# STM_TEST.net
KiCad netlist of a schematic drawn in EAGLE
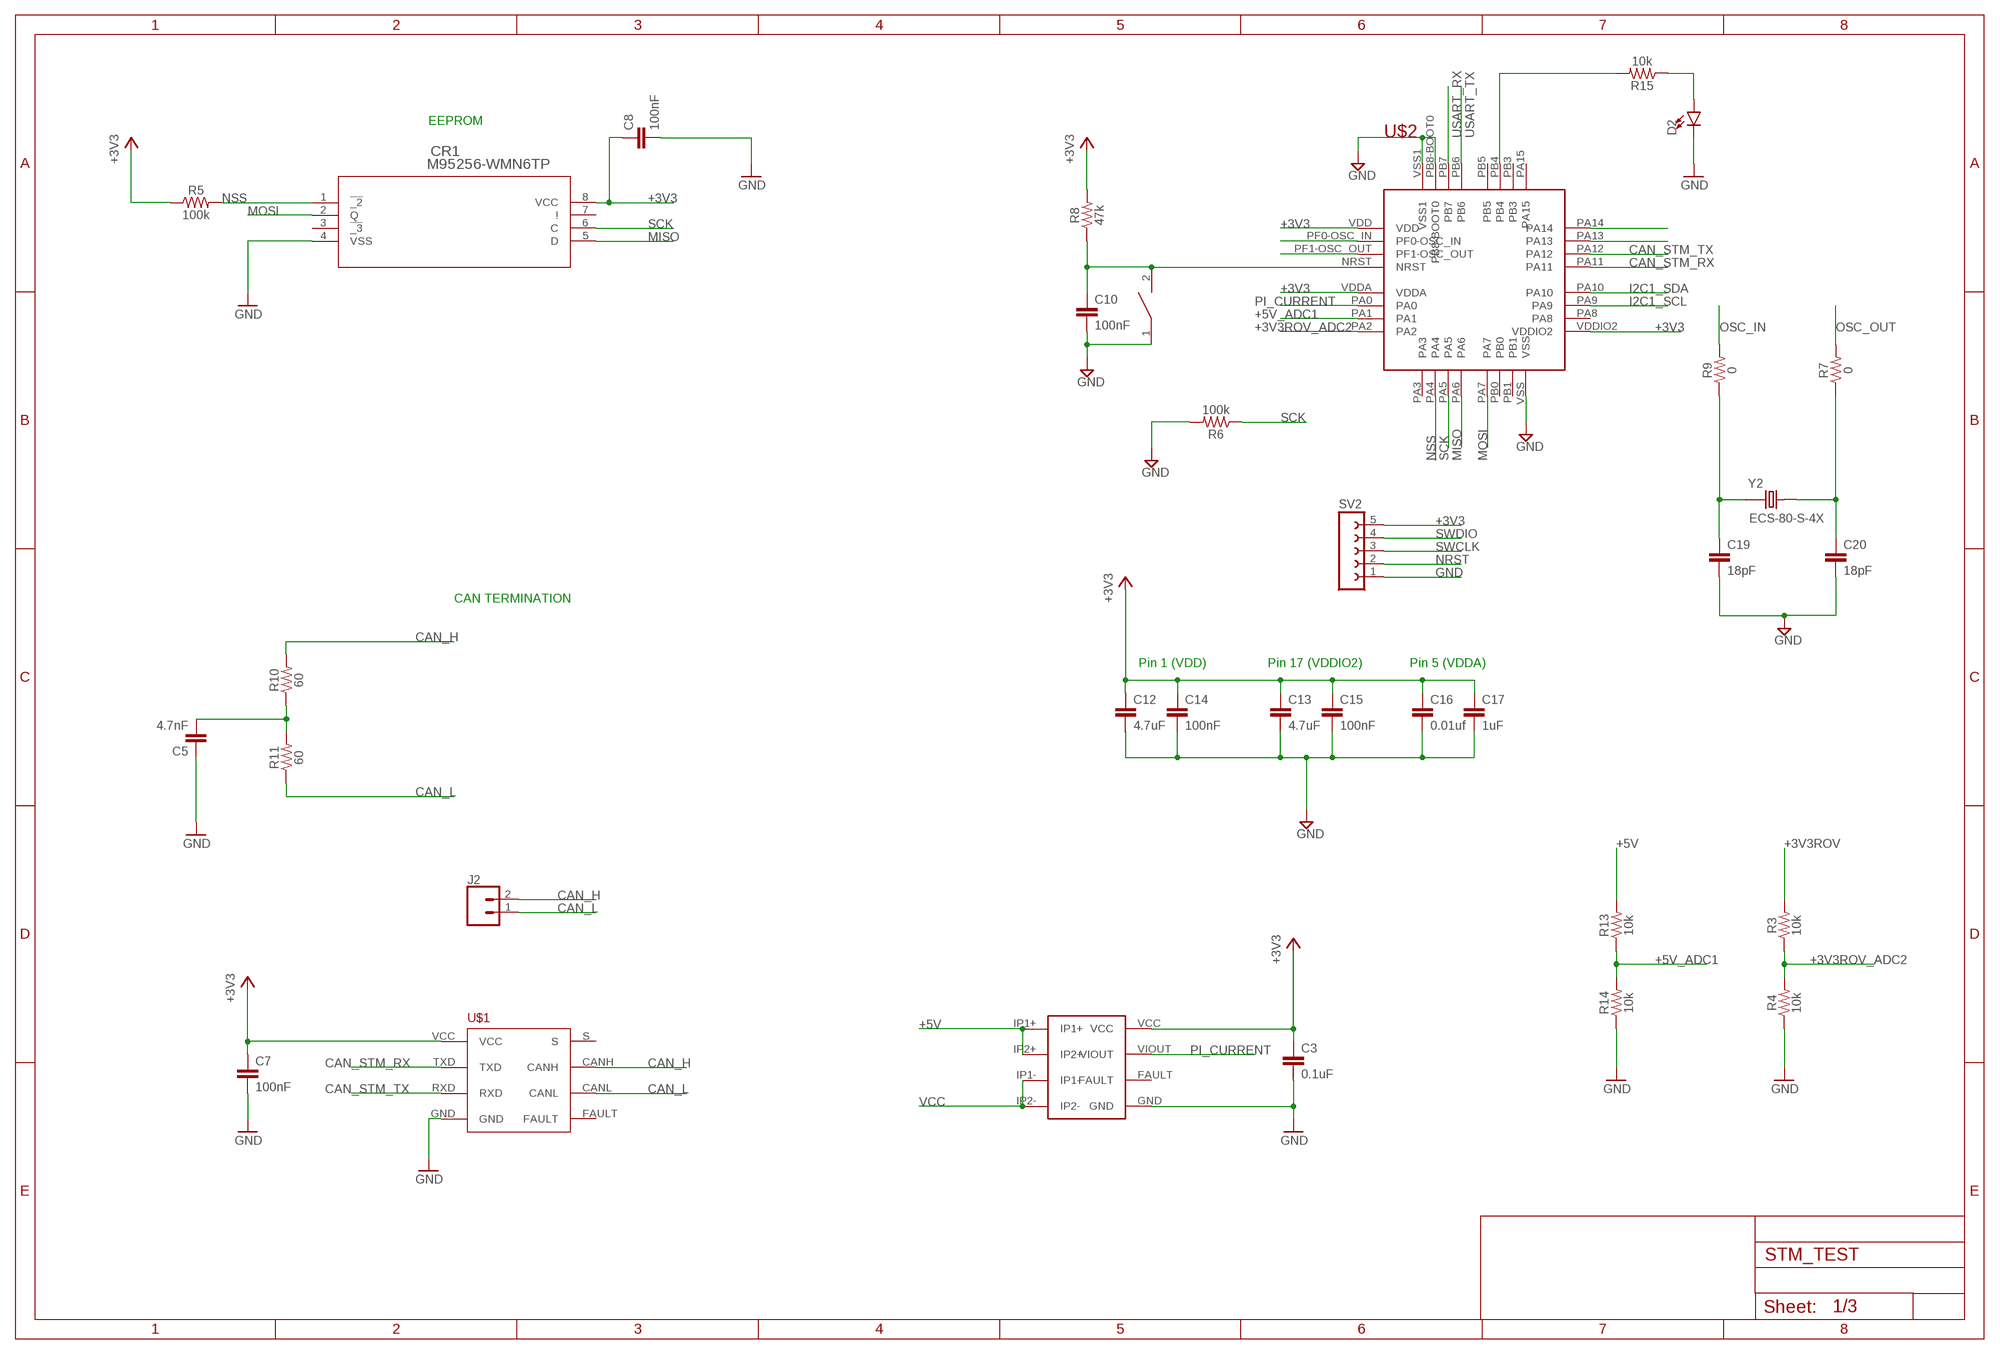
[diagram p0: schematic, sheet 1]
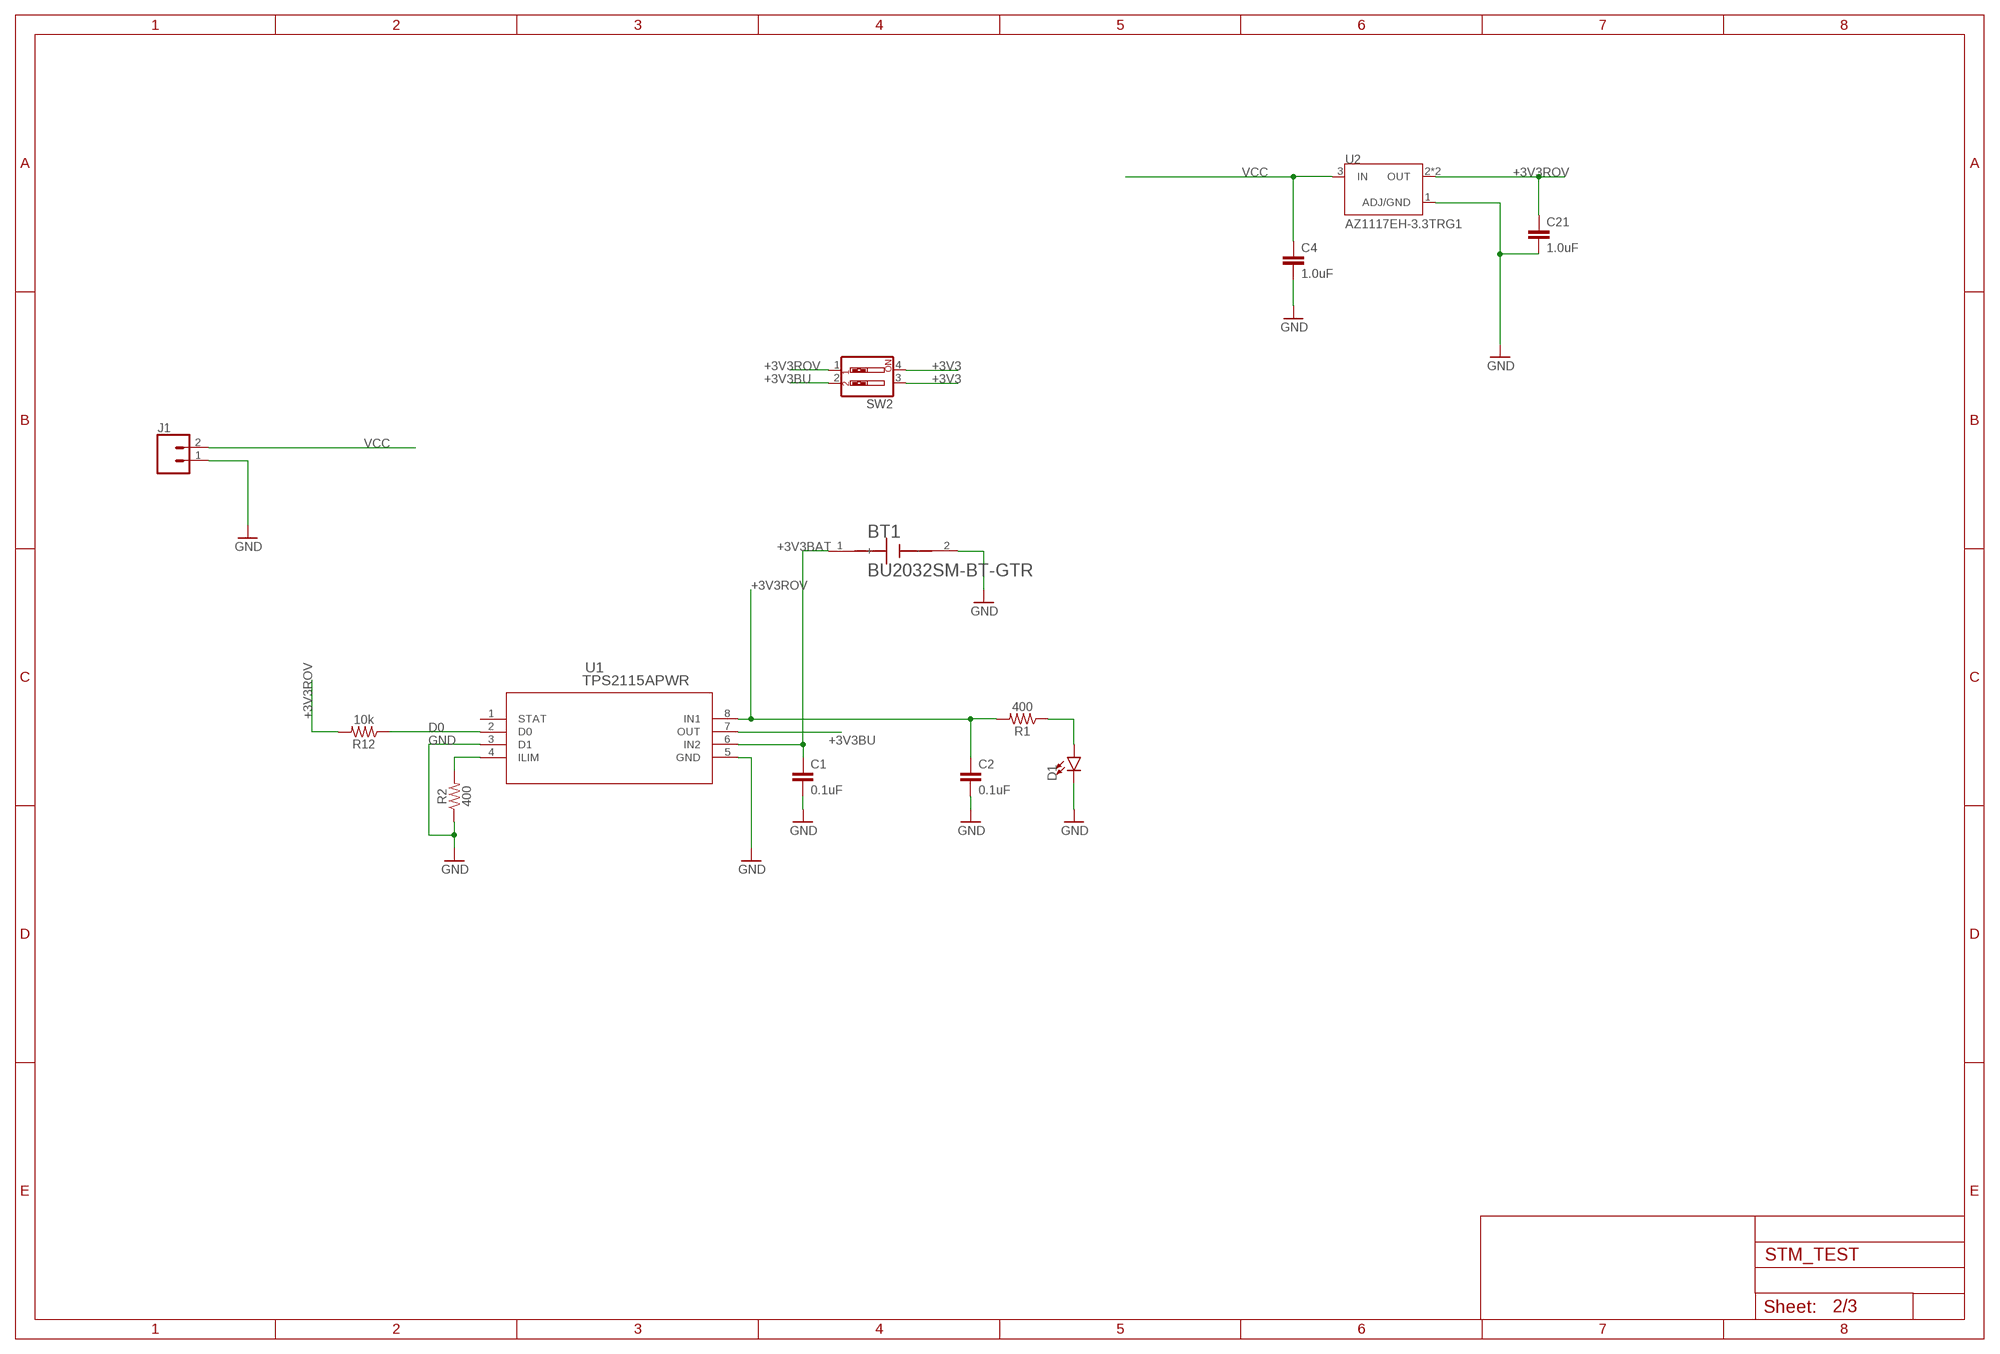
[diagram p1: schematic, sheet 2]
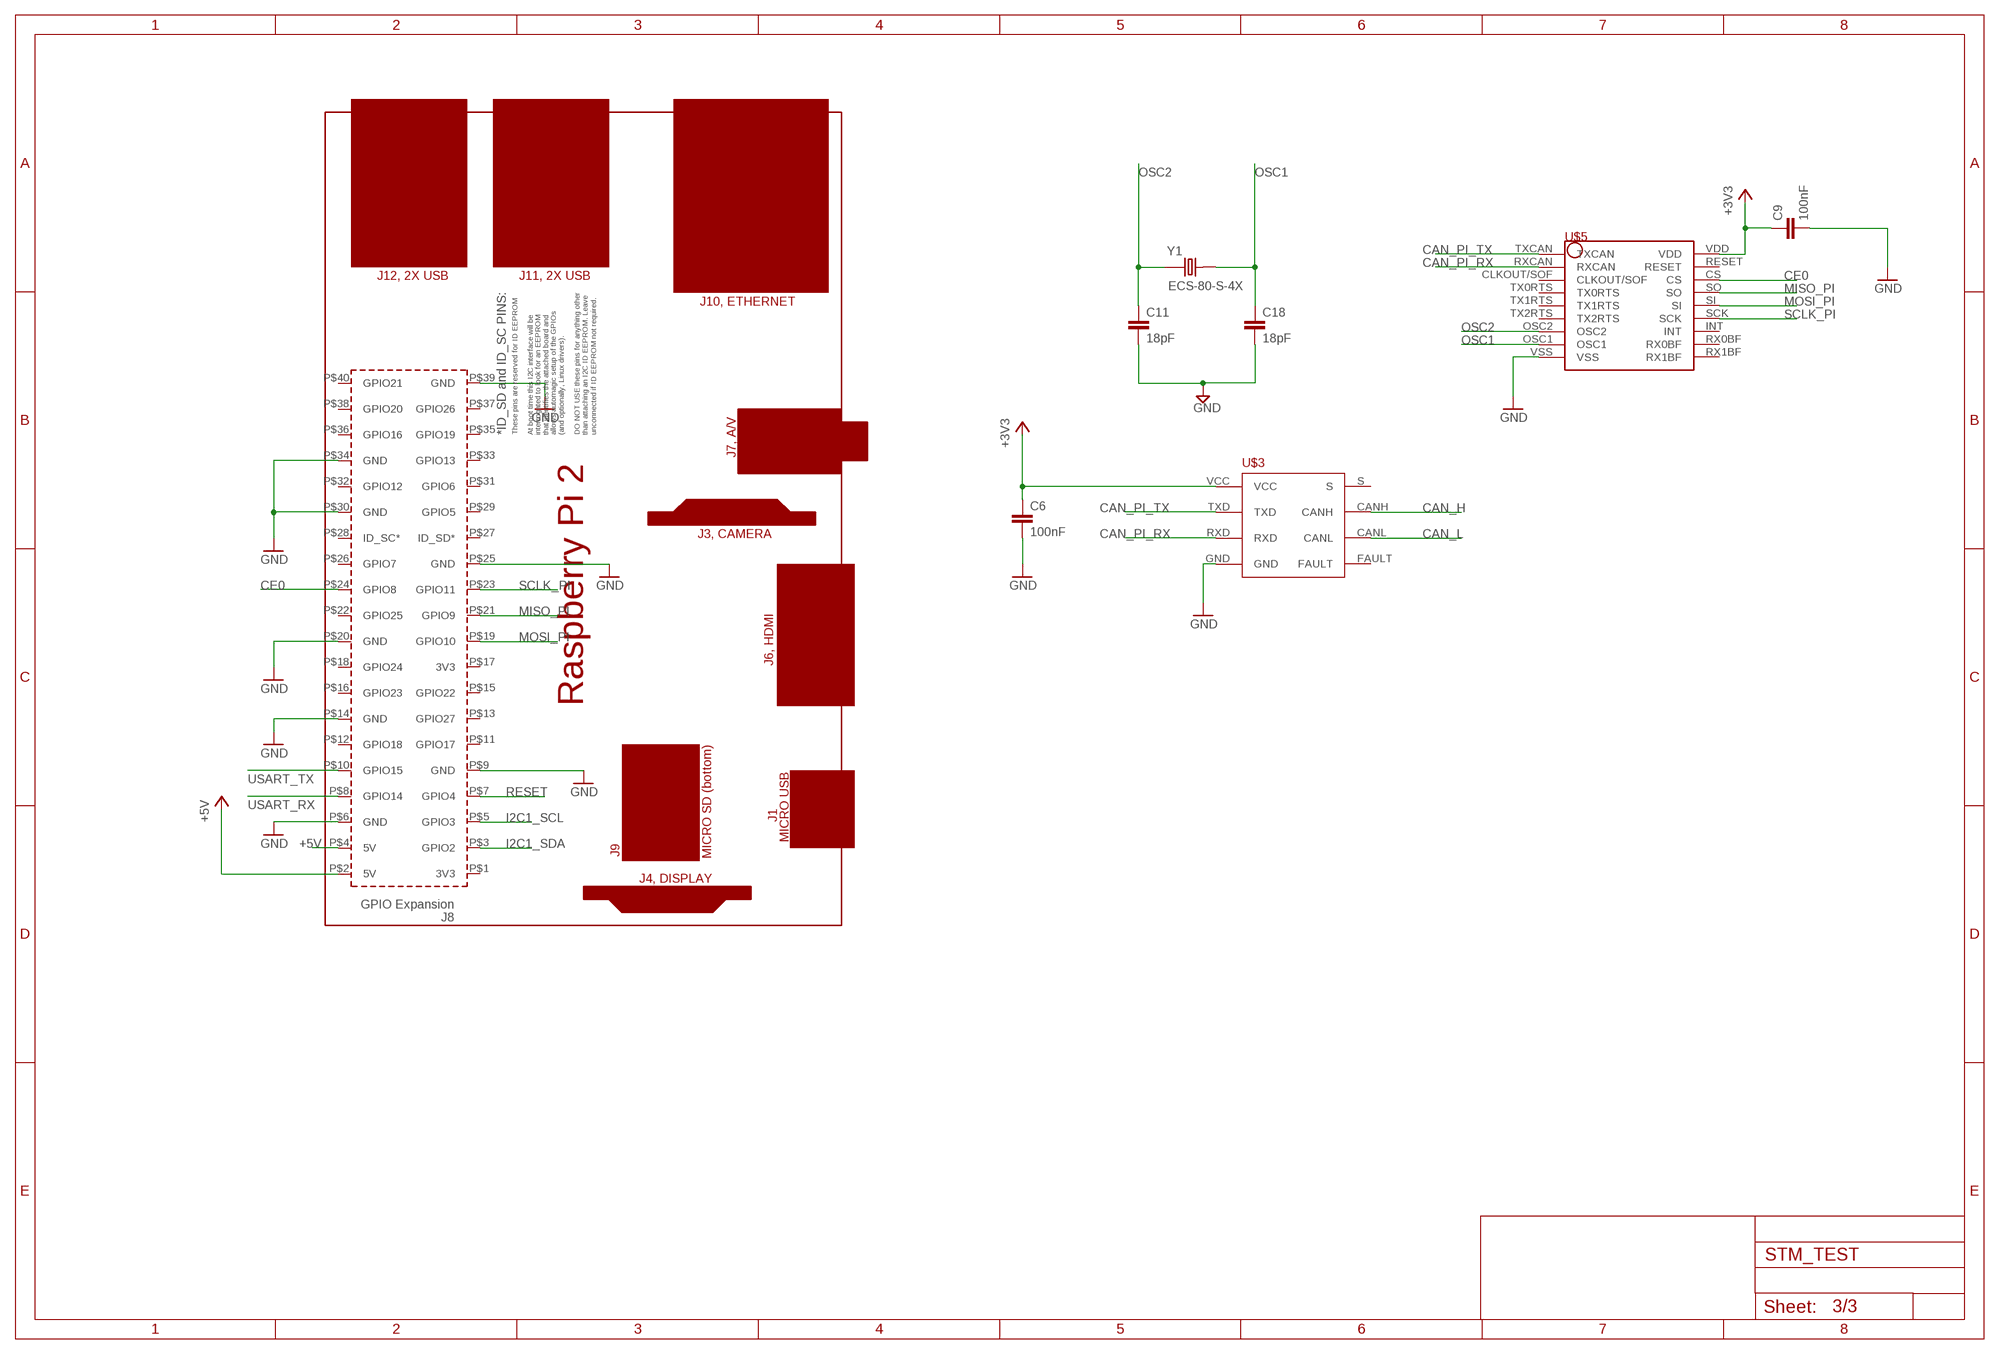
[diagram p2: schematic, sheet 3]

(export (version "E")
  (design (tool "Eeschema 10.0.6"))
  (components
    (comp (ref "C6")
      (value "100nF")
      (footprint "eagle-import:0603")
      (libsource (lib "eagle-import") (part "4.7UF0603"))
    )
    (comp (ref "C9")
      (value "100nF")
      (footprint "eagle-import:0603")
      (libsource (lib "eagle-import") (part "4.7UF0603"))
    )
    (comp (ref "C11")
      (value "18pF")
      (footprint "eagle-import:0603")
      (libsource (lib "eagle-import") (part "4.7UF0603"))
    )
    (comp (ref "C18")
      (value "18pF")
      (footprint "eagle-import:0603")
      (libsource (lib "eagle-import") (part "4.7UF0603"))
    )
    (comp (ref "PCB1")
      (value "RPI2")
      (footprint "eagle-import:RPI2")
      (libsource (lib "eagle-import") (part "RPI2"))
    )
    (comp (ref "U$3")
      (value "TCAN337D")
      (footprint "eagle-import:TCAN337D")
      (libsource (lib "eagle-import") (part "TCAN337D"))
    )
    (comp (ref "U$5")
      (value "MCP2515")
      (footprint "eagle-import:MCP2515")
      (libsource (lib "eagle-import") (part "MCP2515"))
    )
    (comp (ref "Y1")
      (value "ECS-80-S-4X")
      (footprint "eagle-import:XTAL_ECS-80-S-4X")
      (fields (field (name "DIGI-KEY_PART_NUMBER") "X1057-ND") (field (name "MF") "ECS International"))
      (libsource (lib "eagle-import") (part "ECS-80-S-4X"))
    )
    (comp (ref "C3")
      (value "0.1uF")
      (footprint "eagle-import:0603")
      (libsource (lib "eagle-import") (part "4.7UF0603"))
    )
    (comp (ref "C5")
      (value "4.7nF")
      (footprint "eagle-import:0603")
      (libsource (lib "eagle-import") (part "0.1UF-0603-25V-(+80/-20%)"))
    )
    (comp (ref "C7")
      (value "100nF")
      (footprint "eagle-import:0603")
      (libsource (lib "eagle-import") (part "4.7UF0603"))
    )
    (comp (ref "C8")
      (value "100nF")
      (footprint "eagle-import:0603")
      (libsource (lib "eagle-import") (part "4.7UF0603"))
    )
    (comp (ref "C10")
      (value "100nF")
      (footprint "eagle-import:0603")
      (libsource (lib "eagle-import") (part "4.7UF0603"))
    )
    (comp (ref "C12")
      (value "4.7uF")
      (footprint "eagle-import:0603")
      (libsource (lib "eagle-import") (part "4.7UF0603"))
    )
    (comp (ref "C13")
      (value "4.7uF")
      (footprint "eagle-import:0603")
      (libsource (lib "eagle-import") (part "4.7UF0603"))
    )
    (comp (ref "C14")
      (value "100nF")
      (footprint "eagle-import:0603")
      (libsource (lib "eagle-import") (part "4.7UF0603"))
    )
    (comp (ref "C15")
      (value "100nF")
      (footprint "eagle-import:0603")
      (libsource (lib "eagle-import") (part "4.7UF0603"))
    )
    (comp (ref "C16")
      (value "0.01uf")
      (footprint "eagle-import:0603")
      (libsource (lib "eagle-import") (part "4.7UF0603"))
    )
    (comp (ref "C17")
      (value "1uF")
      (footprint "eagle-import:0603")
      (libsource (lib "eagle-import") (part "4.7UF0603"))
    )
    (comp (ref "C19")
      (value "18pF")
      (footprint "eagle-import:0603")
      (libsource (lib "eagle-import") (part "4.7UF0603"))
    )
    (comp (ref "C20")
      (value "18pF")
      (footprint "eagle-import:0603")
      (libsource (lib "eagle-import") (part "4.7UF0603"))
    )
    (comp (ref "CR1")
      (value "M95256-WMN6TP")
      (footprint "eagle-import:SO-8")
      (fields (field (name "MANUFACTURER_PART_NUMBER") "M95256WMN6TP"))
      (libsource (lib "eagle-import") (part "M95256-WMN6TP"))
    )
    (comp (ref "D2")
      (value "LED0603")
      (footprint "eagle-import:LED-0603")
      (libsource (lib "eagle-import") (part "LED0603"))
    )
    (comp (ref "J2")
      (value "CONN_02")
      (footprint "eagle-import:1X02")
      (libsource (lib "eagle-import") (part "CONN_02"))
    )
    (comp (ref "R3")
      (value "10k")
      (footprint "eagle-import:0603")
      (libsource (lib "eagle-import") (part "1KOHM-0603-1/10W-1%"))
    )
    (comp (ref "R4")
      (value "10k")
      (footprint "eagle-import:0603")
      (libsource (lib "eagle-import") (part "1KOHM-0603-1/10W-1%"))
    )
    (comp (ref "R5")
      (value "100k")
      (footprint "eagle-import:0603")
      (libsource (lib "eagle-import") (part "1KOHM-0603-1/10W-1%"))
    )
    (comp (ref "R6")
      (value "100k")
      (footprint "eagle-import:0603")
      (libsource (lib "eagle-import") (part "1KOHM-0603-1/10W-1%"))
    )
    (comp (ref "R7")
      (value "0")
      (footprint "eagle-import:0603")
      (libsource (lib "eagle-import") (part "1KOHM-0603-1/10W-1%"))
    )
    (comp (ref "R8")
      (value "47k")
      (footprint "eagle-import:0603")
      (libsource (lib "eagle-import") (part "1KOHM-0603-1/10W-1%"))
    )
    (comp (ref "R9")
      (value "0")
      (footprint "eagle-import:0603")
      (libsource (lib "eagle-import") (part "1KOHM-0603-1/10W-1%"))
    )
    (comp (ref "R10")
      (value "60")
      (footprint "eagle-import:0603")
      (libsource (lib "eagle-import") (part "1KOHM-0603-1/10W-1%"))
    )
    (comp (ref "R11")
      (value "60")
      (footprint "eagle-import:0603")
      (libsource (lib "eagle-import") (part "1KOHM-0603-1/10W-1%"))
    )
    (comp (ref "R13")
      (value "10k")
      (footprint "eagle-import:0603")
      (libsource (lib "eagle-import") (part "1KOHM-0603-1/10W-1%"))
    )
    (comp (ref "R14")
      (value "10k")
      (footprint "eagle-import:0603")
      (libsource (lib "eagle-import") (part "1KOHM-0603-1/10W-1%"))
    )
    (comp (ref "R15")
      (value "10k")
      (footprint "eagle-import:0603")
      (libsource (lib "eagle-import") (part "100KOHM-0603-1/10W-1%"))
    )
    (comp (ref "RESET1")
      (value "SWITCH")
      (footprint "eagle-import:SW_2512")
      (libsource (lib "eagle-import") (part "SWITCH"))
    )
    (comp (ref "SV2")
      (value "FE05-1")
      (footprint "eagle-import:FE05-1")
      (libsource (lib "eagle-import") (part "FE05-1"))
    )
    (comp (ref "U$1")
      (value "TCAN337D")
      (footprint "eagle-import:TCAN337D")
      (libsource (lib "eagle-import") (part "TCAN337D"))
    )
    (comp (ref "U$2")
      (value "STM32F042K6T6")
      (footprint "eagle-import:STM32F042K6T6")
      (libsource (lib "eagle-import") (part "STM32F042K6T6"))
    )
    (comp (ref "U$4")
      (value "ACS711")
      (footprint "eagle-import:ACS711")
      (libsource (lib "eagle-import") (part "ACS711"))
    )
    (comp (ref "Y2")
      (value "ECS-80-S-4X")
      (footprint "eagle-import:XTAL_ECS-80-S-4X")
      (fields (field (name "DIGI-KEY_PART_NUMBER") "X1057-ND") (field (name "MF") "ECS International"))
      (libsource (lib "eagle-import") (part "ECS-80-S-4X"))
    )
    (comp (ref "BT1")
      (value "BU2032SM-BT-GTR")
      (footprint "eagle-import:BAT_BU2032SM-BT-GTR")
      (fields (field (name "DIGI-KEY_PART_NUMBER") "BU2032SM-BT-GCT-ND") (field (name "MF") "MPD"))
      (libsource (lib "eagle-import") (part "BU2032SM-BT-GTR"))
    )
    (comp (ref "C1")
      (value "0.1uF")
      (footprint "eagle-import:0603")
      (libsource (lib "eagle-import") (part "0.1UF-0603-25V-(+80/-20%)"))
    )
    (comp (ref "C2")
      (value "0.1uF")
      (footprint "eagle-import:0603")
      (libsource (lib "eagle-import") (part "0.1UF-0603-25V-(+80/-20%)"))
    )
    (comp (ref "C4")
      (value "1.0uF")
      (footprint "eagle-import:0603")
      (libsource (lib "eagle-import") (part "1.0UF-0603-16V-10%"))
    )
    (comp (ref "C21")
      (value "1.0uF")
      (footprint "eagle-import:0603")
      (libsource (lib "eagle-import") (part "1.0UF-0603-16V-10%"))
    )
    (comp (ref "D1")
      (value "LED0603")
      (footprint "eagle-import:LED-0603")
      (libsource (lib "eagle-import") (part "LED0603"))
    )
    (comp (ref "J1")
      (value "CONN_02")
      (footprint "eagle-import:1X02")
      (libsource (lib "eagle-import") (part "CONN_02"))
    )
    (comp (ref "R1")
      (value "400")
      (footprint "eagle-import:0603")
      (libsource (lib "eagle-import") (part "100KOHM-0603-1/10W-1%"))
    )
    (comp (ref "R2")
      (value "400")
      (footprint "eagle-import:0603")
      (libsource (lib "eagle-import") (part "100KOHM-0603-1/10W-1%"))
    )
    (comp (ref "R12")
      (value "10k")
      (footprint "eagle-import:0603")
      (libsource (lib "eagle-import") (part "100KOHM-0603-1/10W-1%"))
    )
    (comp (ref "SW2")
      (value "SW_DIP-2")
      (footprint "eagle-import:EDG-02")
      (libsource (lib "eagle-import") (part "SW_DIP-2"))
    )
    (comp (ref "U1")
      (value "TPS2115APWR")
      (footprint "eagle-import:PW8")
      (libsource (lib "eagle-import") (part "TPS2115APWR"))
    )
    (comp (ref "U2")
      (value "AZ1117EH-3.3TRG1")
      (footprint "eagle-import:SOT230P700X180-4N")
      (fields (field (name "MF") "Diodes Inc."))
      (libsource (lib "eagle-import") (part "AZ1117EH-3.3TRG1"))
    )
  )
  (nets
    (net (code "1") (name "+3V3") (class "Default")
      (node (ref "C12") (pin "1") (pinfunction "1_1") (pintype "passive"))
      (node (ref "C13") (pin "1") (pinfunction "1_1") (pintype "passive"))
      (node (ref "C14") (pin "1") (pinfunction "1_1") (pintype "passive"))
      (node (ref "C15") (pin "1") (pinfunction "1_1") (pintype "passive"))
      (node (ref "C16") (pin "1") (pinfunction "1_1") (pintype "passive"))
      (node (ref "C17") (pin "1") (pinfunction "1_1") (pintype "passive"))
      (node (ref "C3") (pin "1") (pinfunction "1_1") (pintype "passive"))
      (node (ref "C6") (pin "1") (pinfunction "1_1") (pintype "passive"))
      (node (ref "C7") (pin "1") (pinfunction "1_1") (pintype "passive"))
      (node (ref "C8") (pin "1") (pinfunction "1_1") (pintype "passive"))
      (node (ref "C9") (pin "1") (pinfunction "1_1") (pintype "passive"))
      (node (ref "CR1") (pin "8") (pinfunction "VCC_8") (pintype "power_in"))
      (node (ref "R5") (pin "1") (pinfunction "1_1") (pintype "passive"))
      (node (ref "R8") (pin "2") (pinfunction "2_2") (pintype "passive"))
      (node (ref "SV2") (pin "5") (pinfunction "5_5") (pintype "passive"))
      (node (ref "SW2") (pin "3") (pinfunction "3_3") (pintype "passive"))
      (node (ref "SW2") (pin "4") (pinfunction "4_4") (pintype "passive"))
      (node (ref "U$1") (pin "VCC") (pinfunction "VCC_VCC") (pintype "bidirectional"))
      (node (ref "U$2") (pin "VDD") (pinfunction "VDD_VDD") (pintype "bidirectional"))
      (node (ref "U$2") (pin "VDDA") (pinfunction "VDDA_VDDA") (pintype "bidirectional"))
      (node (ref "U$2") (pin "VDDIO2") (pinfunction "VDDIO2_VDDIO2") (pintype "bidirectional"))
      (node (ref "U$3") (pin "VCC") (pinfunction "VCC_VCC") (pintype "bidirectional"))
      (node (ref "U$4") (pin "VCC") (pinfunction "VCC_VCC") (pintype "bidirectional"))
      (node (ref "U$5") (pin "VDD") (pinfunction "VDD_VDD") (pintype "bidirectional"))
    )
    (net (code "2") (name "+3V3BAT") (class "Default")
      (node (ref "BT1") (pin "1") (pinfunction "+_1") (pintype "passive"))
      (node (ref "C1") (pin "1") (pinfunction "1_1") (pintype "passive"))
      (node (ref "U1") (pin "6") (pinfunction "IN2_6") (pintype "input"))
    )
    (net (code "3") (name "+3V3BU") (class "Default")
      (node (ref "SW2") (pin "2") (pinfunction "2_2") (pintype "passive"))
      (node (ref "U1") (pin "7") (pinfunction "OUT_7") (pintype "output"))
    )
    (net (code "4") (name "+3V3ROV") (class "Default")
      (node (ref "C2") (pin "1") (pinfunction "1_1") (pintype "passive"))
      (node (ref "C21") (pin "1") (pinfunction "1_1") (pintype "passive"))
      (node (ref "R1") (pin "2") (pinfunction "2_2") (pintype "passive"))
      (node (ref "R12") (pin "2") (pinfunction "2_2") (pintype "passive"))
      (node (ref "R3") (pin "2") (pinfunction "2_2") (pintype "passive"))
      (node (ref "SW2") (pin "1") (pinfunction "1_1") (pintype "passive"))
      (node (ref "U1") (pin "8") (pinfunction "IN1_8") (pintype "input"))
      (node (ref "U2") (pin "2") (pinfunction "OUT_2") (pintype "output"))
      (node (ref "U2") (pin "4") (pinfunction "OUT_4") (pintype "output"))
    )
    (net (code "5") (name "+3V3ROV_ADC2") (class "Default")
      (node (ref "R3") (pin "1") (pinfunction "1_1") (pintype "passive"))
      (node (ref "R4") (pin "2") (pinfunction "2_2") (pintype "passive"))
      (node (ref "U$2") (pin "PA2") (pinfunction "PA2_PA2") (pintype "bidirectional"))
    )
    (net (code "6") (name "+5V") (class "Default")
      (node (ref "PCB1") (pin "P$2") (pinfunction "5V_P$2") (pintype "bidirectional"))
      (node (ref "PCB1") (pin "P$4") (pinfunction "5V_P$4") (pintype "bidirectional"))
      (node (ref "R13") (pin "2") (pinfunction "2_2") (pintype "passive"))
      (node (ref "U$4") (pin "IP1+") (pinfunction "IP1+_IP1+") (pintype "bidirectional"))
      (node (ref "U$4") (pin "IP2+") (pinfunction "IP2+_IP2+") (pintype "bidirectional"))
    )
    (net (code "7") (name "+5V_ADC1") (class "Default")
      (node (ref "R13") (pin "1") (pinfunction "1_1") (pintype "passive"))
      (node (ref "R14") (pin "2") (pinfunction "2_2") (pintype "passive"))
      (node (ref "U$2") (pin "PA1") (pinfunction "PA1_PA1") (pintype "bidirectional"))
    )
    (net (code "8") (name "CAN_H") (class "Default")
      (node (ref "J2") (pin "2") (pinfunction "2_2") (pintype "passive"))
      (node (ref "R10") (pin "2") (pinfunction "2_2") (pintype "passive"))
      (node (ref "U$1") (pin "CANH") (pinfunction "CANH_CANH") (pintype "bidirectional"))
      (node (ref "U$3") (pin "CANH") (pinfunction "CANH_CANH") (pintype "bidirectional"))
    )
    (net (code "9") (name "CAN_L") (class "Default")
      (node (ref "J2") (pin "1") (pinfunction "1_1") (pintype "passive"))
      (node (ref "R11") (pin "1") (pinfunction "1_1") (pintype "passive"))
      (node (ref "U$1") (pin "CANL") (pinfunction "CANL_CANL") (pintype "bidirectional"))
      (node (ref "U$3") (pin "CANL") (pinfunction "CANL_CANL") (pintype "bidirectional"))
    )
    (net (code "10") (name "CAN_PI_RX") (class "Default")
      (node (ref "U$3") (pin "RXD") (pinfunction "RXD_RXD") (pintype "bidirectional"))
      (node (ref "U$5") (pin "RXCAN") (pinfunction "RXCAN_RXCAN") (pintype "bidirectional"))
    )
    (net (code "11") (name "CAN_PI_TX") (class "Default")
      (node (ref "U$3") (pin "TXD") (pinfunction "TXD_TXD") (pintype "bidirectional"))
      (node (ref "U$5") (pin "TXCAN") (pinfunction "TXCAN_TXCAN") (pintype "bidirectional"))
    )
    (net (code "12") (name "CAN_STM_RX") (class "Default")
      (node (ref "U$1") (pin "TXD") (pinfunction "TXD_TXD") (pintype "bidirectional"))
      (node (ref "U$2") (pin "PA11") (pinfunction "PA11_PA11") (pintype "bidirectional"))
    )
    (net (code "13") (name "CAN_STM_TX") (class "Default")
      (node (ref "U$1") (pin "RXD") (pinfunction "RXD_RXD") (pintype "bidirectional"))
      (node (ref "U$2") (pin "PA12") (pinfunction "PA12_PA12") (pintype "bidirectional"))
    )
    (net (code "14") (name "CE0") (class "Default")
      (node (ref "PCB1") (pin "P$24") (pinfunction "GPIO8_P$24") (pintype "bidirectional"))
      (node (ref "U$5") (pin "CS") (pinfunction "CS_CS") (pintype "bidirectional"))
    )
    (net (code "15") (name "D0") (class "Default")
      (node (ref "R12") (pin "1") (pinfunction "1_1") (pintype "passive"))
      (node (ref "U1") (pin "2") (pinfunction "D0_2") (pintype "input"))
    )
    (net (code "16") (name "GND") (class "Default")
      (node (ref "BT1") (pin "2") (pinfunction "-_2") (pintype "passive"))
      (node (ref "C1") (pin "2") (pinfunction "2_2") (pintype "passive"))
      (node (ref "C10") (pin "2") (pinfunction "2_2") (pintype "passive"))
      (node (ref "C11") (pin "2") (pinfunction "2_2") (pintype "passive"))
      (node (ref "C12") (pin "2") (pinfunction "2_2") (pintype "passive"))
      (node (ref "C13") (pin "2") (pinfunction "2_2") (pintype "passive"))
      (node (ref "C14") (pin "2") (pinfunction "2_2") (pintype "passive"))
      (node (ref "C15") (pin "2") (pinfunction "2_2") (pintype "passive"))
      (node (ref "C16") (pin "2") (pinfunction "2_2") (pintype "passive"))
      (node (ref "C17") (pin "2") (pinfunction "2_2") (pintype "passive"))
      (node (ref "C18") (pin "2") (pinfunction "2_2") (pintype "passive"))
      (node (ref "C19") (pin "2") (pinfunction "2_2") (pintype "passive"))
      (node (ref "C2") (pin "2") (pinfunction "2_2") (pintype "passive"))
      (node (ref "C20") (pin "2") (pinfunction "2_2") (pintype "passive"))
      (node (ref "C21") (pin "2") (pinfunction "2_2") (pintype "passive"))
      (node (ref "C3") (pin "2") (pinfunction "2_2") (pintype "passive"))
      (node (ref "C4") (pin "2") (pinfunction "2_2") (pintype "passive"))
      (node (ref "C5") (pin "1") (pinfunction "1_1") (pintype "passive"))
      (node (ref "C6") (pin "2") (pinfunction "2_2") (pintype "passive"))
      (node (ref "C7") (pin "2") (pinfunction "2_2") (pintype "passive"))
      (node (ref "C8") (pin "2") (pinfunction "2_2") (pintype "passive"))
      (node (ref "C9") (pin "2") (pinfunction "2_2") (pintype "passive"))
      (node (ref "CR1") (pin "4") (pinfunction "VSS_4") (pintype "power_in"))
      (node (ref "D1") (pin "C") (pinfunction "C_C") (pintype "passive"))
      (node (ref "D2") (pin "C") (pinfunction "C_C") (pintype "passive"))
      (node (ref "J1") (pin "1") (pinfunction "1_1") (pintype "passive"))
      (node (ref "PCB1") (pin "P$14") (pinfunction "GND_P$14") (pintype "bidirectional"))
      (node (ref "PCB1") (pin "P$20") (pinfunction "GND_P$20") (pintype "bidirectional"))
      (node (ref "PCB1") (pin "P$25") (pinfunction "GND_P$25") (pintype "bidirectional"))
      (node (ref "PCB1") (pin "P$30") (pinfunction "GND_P$30") (pintype "bidirectional"))
      (node (ref "PCB1") (pin "P$34") (pinfunction "GND_P$34") (pintype "bidirectional"))
      (node (ref "PCB1") (pin "P$39") (pinfunction "GND_P$39") (pintype "bidirectional"))
      (node (ref "PCB1") (pin "P$6") (pinfunction "GND_P$6") (pintype "bidirectional"))
      (node (ref "PCB1") (pin "P$9") (pinfunction "GND_P$9") (pintype "bidirectional"))
      (node (ref "R14") (pin "1") (pinfunction "1_1") (pintype "passive"))
      (node (ref "R2") (pin "1") (pinfunction "1_1") (pintype "passive"))
      (node (ref "R4") (pin "1") (pinfunction "1_1") (pintype "passive"))
      (node (ref "R6") (pin "2") (pinfunction "2_2") (pintype "passive"))
      (node (ref "RESET1") (pin "1") (pinfunction "P$1_1") (pintype "bidirectional"))
      (node (ref "SV2") (pin "1") (pinfunction "1_1") (pintype "passive"))
      (node (ref "U$1") (pin "GND") (pinfunction "GND_GND") (pintype "bidirectional"))
      (node (ref "U$2") (pin "PB8-BOOT0") (pinfunction "PB8-BOOT0_PB8-BOOT0") (pintype "bidirectional"))
      (node (ref "U$2") (pin "VSS") (pinfunction "VSS_VSS") (pintype "bidirectional"))
      (node (ref "U$2") (pin "VSS1") (pinfunction "VSS1_VSS1") (pintype "bidirectional"))
      (node (ref "U$3") (pin "GND") (pinfunction "GND_GND") (pintype "bidirectional"))
      (node (ref "U$4") (pin "GND") (pinfunction "GND_GND") (pintype "bidirectional"))
      (node (ref "U$5") (pin "VSS") (pinfunction "VSS_VSS") (pintype "bidirectional"))
      (node (ref "U1") (pin "3") (pinfunction "D1_3") (pintype "input"))
      (node (ref "U1") (pin "5") (pinfunction "GND_5") (pintype "power_in"))
      (node (ref "U2") (pin "1") (pinfunction "ADJ/GND_1") (pintype "power_in"))
    )
    (net (code "17") (name "I2C1_SCL") (class "Default")
      (node (ref "PCB1") (pin "P$5") (pinfunction "GPIO3_P$5") (pintype "bidirectional"))
      (node (ref "U$2") (pin "PA9") (pinfunction "PA9_PA9") (pintype "bidirectional"))
    )
    (net (code "18") (name "I2C1_SDA") (class "Default")
      (node (ref "PCB1") (pin "P$3") (pinfunction "GPIO2_P$3") (pintype "bidirectional"))
      (node (ref "U$2") (pin "PA10") (pinfunction "PA10_PA10") (pintype "bidirectional"))
    )
    (net (code "19") (name "MISO") (class "Default")
      (node (ref "CR1") (pin "5") (pinfunction "D_5") (pintype "input"))
      (node (ref "U$2") (pin "PA6") (pinfunction "PA6_PA6") (pintype "bidirectional"))
    )
    (net (code "20") (name "MISO_PI") (class "Default")
      (node (ref "PCB1") (pin "P$21") (pinfunction "GPIO9_P$21") (pintype "bidirectional"))
      (node (ref "U$5") (pin "SO") (pinfunction "SO_SO") (pintype "bidirectional"))
    )
    (net (code "21") (name "MOSI") (class "Default")
      (node (ref "CR1") (pin "2") (pinfunction "Q_2") (pintype "output"))
      (node (ref "U$2") (pin "PA7") (pinfunction "PA7_PA7") (pintype "bidirectional"))
    )
    (net (code "22") (name "MOSI_PI") (class "Default")
      (node (ref "PCB1") (pin "P$19") (pinfunction "GPIO10_P$19") (pintype "bidirectional"))
      (node (ref "U$5") (pin "SI") (pinfunction "SI_SI") (pintype "bidirectional"))
    )
    (net (code "23") (name "NRST") (class "Default")
      (node (ref "C10") (pin "1") (pinfunction "1_1") (pintype "passive"))
      (node (ref "R8") (pin "1") (pinfunction "1_1") (pintype "passive"))
      (node (ref "RESET1") (pin "2") (pinfunction "P$2_2") (pintype "bidirectional"))
      (node (ref "SV2") (pin "2") (pinfunction "2_2") (pintype "passive"))
      (node (ref "U$2") (pin "NRST") (pinfunction "NRST_NRST") (pintype "bidirectional"))
    )
    (net (code "24") (name "NSS") (class "Default")
      (node (ref "CR1") (pin "1") (pinfunction "~{_2}_1") (pintype "passive"))
      (node (ref "R5") (pin "2") (pinfunction "2_2") (pintype "passive"))
      (node (ref "U$2") (pin "PA4") (pinfunction "PA4_PA4") (pintype "bidirectional"))
    )
    (net (code "25") (name "Net-(C5-Pad2)") (class "Default")
      (node (ref "C5") (pin "2") (pinfunction "2_2") (pintype "passive"))
      (node (ref "R10") (pin "1") (pinfunction "1_1") (pintype "passive"))
      (node (ref "R11") (pin "2") (pinfunction "2_2") (pintype "passive"))
    )
    (net (code "26") (name "Net-(C19-Pad1)") (class "Default")
      (node (ref "C19") (pin "1") (pinfunction "1_1") (pintype "passive"))
      (node (ref "R9") (pin "1") (pinfunction "1_1") (pintype "passive"))
      (node (ref "Y2") (pin "1") (pinfunction "1_1") (pintype "passive"))
    )
    (net (code "27") (name "Net-(C20-Pad1)") (class "Default")
      (node (ref "C20") (pin "1") (pinfunction "1_1") (pintype "passive"))
      (node (ref "R7") (pin "1") (pinfunction "1_1") (pintype "passive"))
      (node (ref "Y2") (pin "2") (pinfunction "2_2") (pintype "passive"))
    )
    (net (code "28") (name "Net-(D1-PadA)") (class "Default")
      (node (ref "D1") (pin "A") (pinfunction "A_A") (pintype "passive"))
      (node (ref "R1") (pin "1") (pinfunction "1_1") (pintype "passive"))
    )
    (net (code "29") (name "Net-(D2-PadA)") (class "Default")
      (node (ref "D2") (pin "A") (pinfunction "A_A") (pintype "passive"))
      (node (ref "R15") (pin "1") (pinfunction "1_1") (pintype "passive"))
    )
    (net (code "30") (name "Net-(R15-Pad2)") (class "Default")
      (node (ref "R15") (pin "2") (pinfunction "2_2") (pintype "passive"))
      (node (ref "U$2") (pin "PB4") (pinfunction "PB4_PB4") (pintype "bidirectional"))
    )
    (net (code "31") (name "Net-(U1-ILIM)") (class "Default")
      (node (ref "R2") (pin "2") (pinfunction "2_2") (pintype "passive"))
      (node (ref "U1") (pin "4") (pinfunction "ILIM_4") (pintype "input"))
    )
    (net (code "32") (name "OSC1") (class "Default")
      (node (ref "C18") (pin "1") (pinfunction "1_1") (pintype "passive"))
      (node (ref "U$5") (pin "OSC1") (pinfunction "OSC1_OSC1") (pintype "bidirectional"))
      (node (ref "Y1") (pin "2") (pinfunction "2_2") (pintype "passive"))
    )
    (net (code "33") (name "OSC2") (class "Default")
      (node (ref "C11") (pin "1") (pinfunction "1_1") (pintype "passive"))
      (node (ref "U$5") (pin "OSC2") (pinfunction "OSC2_OSC2") (pintype "bidirectional"))
      (node (ref "Y1") (pin "1") (pinfunction "1_1") (pintype "passive"))
    )
    (net (code "34") (name "OSC_IN") (class "Default")
      (node (ref "R9") (pin "2") (pinfunction "2_2") (pintype "passive"))
      (node (ref "U$2") (pin "PF0-OSC_IN") (pinfunction "PF0-OSC_IN_PF0-OSC_IN") (pintype "bidirectional"))
    )
    (net (code "35") (name "OSC_OUT") (class "Default")
      (node (ref "R7") (pin "2") (pinfunction "2_2") (pintype "passive"))
      (node (ref "U$2") (pin "PF1-OSC_OUT") (pinfunction "PF1-OSC_OUT_PF1-OSC_OUT") (pintype "bidirectional"))
    )
    (net (code "36") (name "PI_CURRENT") (class "Default")
      (node (ref "U$2") (pin "PA0") (pinfunction "PA0_PA0") (pintype "bidirectional"))
      (node (ref "U$4") (pin "VIOUT") (pinfunction "VIOUT_VIOUT") (pintype "bidirectional"))
    )
    (net (code "37") (name "RESET") (class "Default")
      (node (ref "PCB1") (pin "P$7") (pinfunction "GPIO4_P$7") (pintype "bidirectional"))
    )
    (net (code "38") (name "SCK") (class "Default")
      (node (ref "CR1") (pin "6") (pinfunction "C_6") (pintype "passive"))
      (node (ref "R6") (pin "1") (pinfunction "1_1") (pintype "passive"))
      (node (ref "U$2") (pin "PA5") (pinfunction "PA5_PA5") (pintype "bidirectional"))
    )
    (net (code "39") (name "SCLK_PI") (class "Default")
      (node (ref "PCB1") (pin "P$23") (pinfunction "GPIO11_P$23") (pintype "bidirectional"))
      (node (ref "U$5") (pin "SCK") (pinfunction "SCK_SCK") (pintype "bidirectional"))
    )
    (net (code "40") (name "SWCLK") (class "Default")
      (node (ref "SV2") (pin "3") (pinfunction "3_3") (pintype "passive"))
      (node (ref "U$2") (pin "PA14") (pinfunction "PA14_PA14") (pintype "bidirectional"))
    )
    (net (code "41") (name "SWDIO") (class "Default")
      (node (ref "SV2") (pin "4") (pinfunction "4_4") (pintype "passive"))
      (node (ref "U$2") (pin "PA13") (pinfunction "PA13_PA13") (pintype "bidirectional"))
    )
    (net (code "42") (name "USART_RX") (class "Default")
      (node (ref "PCB1") (pin "P$8") (pinfunction "GPIO14_P$8") (pintype "bidirectional"))
      (node (ref "U$2") (pin "PB7") (pinfunction "PB7_PB7") (pintype "bidirectional"))
    )
    (net (code "43") (name "USART_TX") (class "Default")
      (node (ref "PCB1") (pin "P$10") (pinfunction "GPIO15_P$10") (pintype "bidirectional"))
      (node (ref "U$2") (pin "PB6") (pinfunction "PB6_PB6") (pintype "bidirectional"))
    )
    (net (code "44") (name "VCC") (class "Default")
      (node (ref "C4") (pin "1") (pinfunction "1_1") (pintype "passive"))
      (node (ref "J1") (pin "2") (pinfunction "2_2") (pintype "passive"))
      (node (ref "U$4") (pin "IP1-") (pinfunction "IP1-_IP1-") (pintype "bidirectional"))
      (node (ref "U$4") (pin "IP2-") (pinfunction "IP2-_IP2-") (pintype "bidirectional"))
      (node (ref "U2") (pin "3") (pinfunction "IN_3") (pintype "input"))
    )
    (net (code "45") (name "unconnected-(CR1-~-Pad7)") (class "Default")
      (node (ref "CR1") (pin "7") (pinfunction "~_7") (pintype "passive"))
    )
    (net (code "46") (name "unconnected-(CR1-~{_3}-Pad3)") (class "Default")
      (node (ref "CR1") (pin "3") (pinfunction "~{_3}_3") (pintype "passive"))
    )
    (net (code "47") (name "unconnected-(PCB1-3V3-PadP$1)") (class "Default")
      (node (ref "PCB1") (pin "P$1") (pinfunction "3V3_P$1") (pintype "bidirectional"))
    )
    (net (code "48") (name "unconnected-(PCB1-3V3-PadP$17)") (class "Default")
      (node (ref "PCB1") (pin "P$17") (pinfunction "3V3_P$17") (pintype "bidirectional"))
    )
    (net (code "49") (name "unconnected-(PCB1-GPIO5-PadP$29)") (class "Default")
      (node (ref "PCB1") (pin "P$29") (pinfunction "GPIO5_P$29") (pintype "bidirectional"))
    )
    (net (code "50") (name "unconnected-(PCB1-GPIO6-PadP$31)") (class "Default")
      (node (ref "PCB1") (pin "P$31") (pinfunction "GPIO6_P$31") (pintype "bidirectional"))
    )
    (net (code "51") (name "unconnected-(PCB1-GPIO7-PadP$26)") (class "Default")
      (node (ref "PCB1") (pin "P$26") (pinfunction "GPIO7_P$26") (pintype "bidirectional"))
    )
    (net (code "52") (name "unconnected-(PCB1-GPIO12-PadP$32)") (class "Default")
      (node (ref "PCB1") (pin "P$32") (pinfunction "GPIO12_P$32") (pintype "bidirectional"))
    )
    (net (code "53") (name "unconnected-(PCB1-GPIO13-PadP$33)") (class "Default")
      (node (ref "PCB1") (pin "P$33") (pinfunction "GPIO13_P$33") (pintype "bidirectional"))
    )
    (net (code "54") (name "unconnected-(PCB1-GPIO16-PadP$36)") (class "Default")
      (node (ref "PCB1") (pin "P$36") (pinfunction "GPIO16_P$36") (pintype "bidirectional"))
    )
    (net (code "55") (name "unconnected-(PCB1-GPIO17-PadP$11)") (class "Default")
      (node (ref "PCB1") (pin "P$11") (pinfunction "GPIO17_P$11") (pintype "bidirectional"))
    )
    (net (code "56") (name "unconnected-(PCB1-GPIO18-PadP$12)") (class "Default")
      (node (ref "PCB1") (pin "P$12") (pinfunction "GPIO18_P$12") (pintype "bidirectional"))
    )
    (net (code "57") (name "unconnected-(PCB1-GPIO19-PadP$35)") (class "Default")
      (node (ref "PCB1") (pin "P$35") (pinfunction "GPIO19_P$35") (pintype "bidirectional"))
    )
    (net (code "58") (name "unconnected-(PCB1-GPIO20-PadP$38)") (class "Default")
      (node (ref "PCB1") (pin "P$38") (pinfunction "GPIO20_P$38") (pintype "bidirectional"))
    )
    (net (code "59") (name "unconnected-(PCB1-GPIO21-PadP$40)") (class "Default")
      (node (ref "PCB1") (pin "P$40") (pinfunction "GPIO21_P$40") (pintype "bidirectional"))
    )
    (net (code "60") (name "unconnected-(PCB1-GPIO22-PadP$15)") (class "Default")
      (node (ref "PCB1") (pin "P$15") (pinfunction "GPIO22_P$15") (pintype "bidirectional"))
    )
    (net (code "61") (name "unconnected-(PCB1-GPIO23-PadP$16)") (class "Default")
      (node (ref "PCB1") (pin "P$16") (pinfunction "GPIO23_P$16") (pintype "bidirectional"))
    )
    (net (code "62") (name "unconnected-(PCB1-GPIO24-PadP$18)") (class "Default")
      (node (ref "PCB1") (pin "P$18") (pinfunction "GPIO24_P$18") (pintype "bidirectional"))
    )
    (net (code "63") (name "unconnected-(PCB1-GPIO25-PadP$22)") (class "Default")
      (node (ref "PCB1") (pin "P$22") (pinfunction "GPIO25_P$22") (pintype "bidirectional"))
    )
    (net (code "64") (name "unconnected-(PCB1-GPIO26-PadP$37)") (class "Default")
      (node (ref "PCB1") (pin "P$37") (pinfunction "GPIO26_P$37") (pintype "bidirectional"))
    )
    (net (code "65") (name "unconnected-(PCB1-GPIO27-PadP$13)") (class "Default")
      (node (ref "PCB1") (pin "P$13") (pinfunction "GPIO27_P$13") (pintype "bidirectional"))
    )
    (net (code "66") (name "unconnected-(PCB1-ID_SC*-PadP$28)") (class "Default")
      (node (ref "PCB1") (pin "P$28") (pinfunction "ID_SC*_P$28") (pintype "bidirectional"))
    )
    (net (code "67") (name "unconnected-(PCB1-ID_SD*-PadP$27)") (class "Default")
      (node (ref "PCB1") (pin "P$27") (pinfunction "ID_SD*_P$27") (pintype "bidirectional"))
    )
    (net (code "68") (name "unconnected-(U$1-PadFAULT)") (class "Default")
      (node (ref "U$1") (pin "FAULT") (pinfunction "FAULT_FAULT") (pintype "bidirectional"))
    )
    (net (code "69") (name "unconnected-(U$1-PadS)") (class "Default")
      (node (ref "U$1") (pin "S") (pinfunction "S_S") (pintype "bidirectional"))
    )
    (net (code "70") (name "unconnected-(U$2-PadPA3)") (class "Default")
      (node (ref "U$2") (pin "PA3") (pinfunction "PA3_PA3") (pintype "bidirectional"))
    )
    (net (code "71") (name "unconnected-(U$2-PadPA8)") (class "Default")
      (node (ref "U$2") (pin "PA8") (pinfunction "PA8_PA8") (pintype "bidirectional"))
    )
    (net (code "72") (name "unconnected-(U$2-PadPA15)") (class "Default")
      (node (ref "U$2") (pin "PA15") (pinfunction "PA15_PA15") (pintype "bidirectional"))
    )
    (net (code "73") (name "unconnected-(U$2-PadPB0)") (class "Default")
      (node (ref "U$2") (pin "PB0") (pinfunction "PB0_PB0") (pintype "bidirectional"))
    )
    (net (code "74") (name "unconnected-(U$2-PadPB1)") (class "Default")
      (node (ref "U$2") (pin "PB1") (pinfunction "PB1_PB1") (pintype "bidirectional"))
    )
    (net (code "75") (name "unconnected-(U$2-PadPB3)") (class "Default")
      (node (ref "U$2") (pin "PB3") (pinfunction "PB3_PB3") (pintype "bidirectional"))
    )
    (net (code "76") (name "unconnected-(U$2-PadPB5)") (class "Default")
      (node (ref "U$2") (pin "PB5") (pinfunction "PB5_PB5") (pintype "bidirectional"))
    )
    (net (code "77") (name "unconnected-(U$3-PadFAULT)") (class "Default")
      (node (ref "U$3") (pin "FAULT") (pinfunction "FAULT_FAULT") (pintype "bidirectional"))
    )
    (net (code "78") (name "unconnected-(U$3-PadS)") (class "Default")
      (node (ref "U$3") (pin "S") (pinfunction "S_S") (pintype "bidirectional"))
    )
    (net (code "79") (name "unconnected-(U$4-PadFAULT)") (class "Default")
      (node (ref "U$4") (pin "FAULT") (pinfunction "FAULT_FAULT") (pintype "bidirectional"))
    )
    (net (code "80") (name "unconnected-(U$5-PadCLKOUT{slash}SOF)") (class "Default")
      (node (ref "U$5") (pin "CLKOUT/SOF") (pinfunction "CLKOUT/SOF_CLKOUT/SOF") (pintype "bidirectional"))
    )
    (net (code "81") (name "unconnected-(U$5-PadINT)") (class "Default")
      (node (ref "U$5") (pin "INT") (pinfunction "INT_INT") (pintype "bidirectional"))
    )
    (net (code "82") (name "unconnected-(U$5-PadRESET)") (class "Default")
      (node (ref "U$5") (pin "RESET") (pinfunction "RESET_RESET") (pintype "bidirectional"))
    )
    (net (code "83") (name "unconnected-(U$5-PadRX0BF)") (class "Default")
      (node (ref "U$5") (pin "RX0BF") (pinfunction "RX0BF_RX0BF") (pintype "bidirectional"))
    )
    (net (code "84") (name "unconnected-(U$5-PadRX1BF)") (class "Default")
      (node (ref "U$5") (pin "RX1BF") (pinfunction "RX1BF_RX1BF") (pintype "bidirectional"))
    )
    (net (code "85") (name "unconnected-(U$5-PadTX0RTS)") (class "Default")
      (node (ref "U$5") (pin "TX0RTS") (pinfunction "TX0RTS_TX0RTS") (pintype "bidirectional"))
    )
    (net (code "86") (name "unconnected-(U$5-PadTX1RTS)") (class "Default")
      (node (ref "U$5") (pin "TX1RTS") (pinfunction "TX1RTS_TX1RTS") (pintype "bidirectional"))
    )
    (net (code "87") (name "unconnected-(U$5-PadTX2RTS)") (class "Default")
      (node (ref "U$5") (pin "TX2RTS") (pinfunction "TX2RTS_TX2RTS") (pintype "bidirectional"))
    )
    (net (code "88") (name "unconnected-(U1-STAT-Pad1)") (class "Default")
      (node (ref "U1") (pin "1") (pinfunction "STAT_1") (pintype "output"))
    )
  )
)
